# MP-Support.net
KiCad netlist of a schematic drawn in Altium Designer
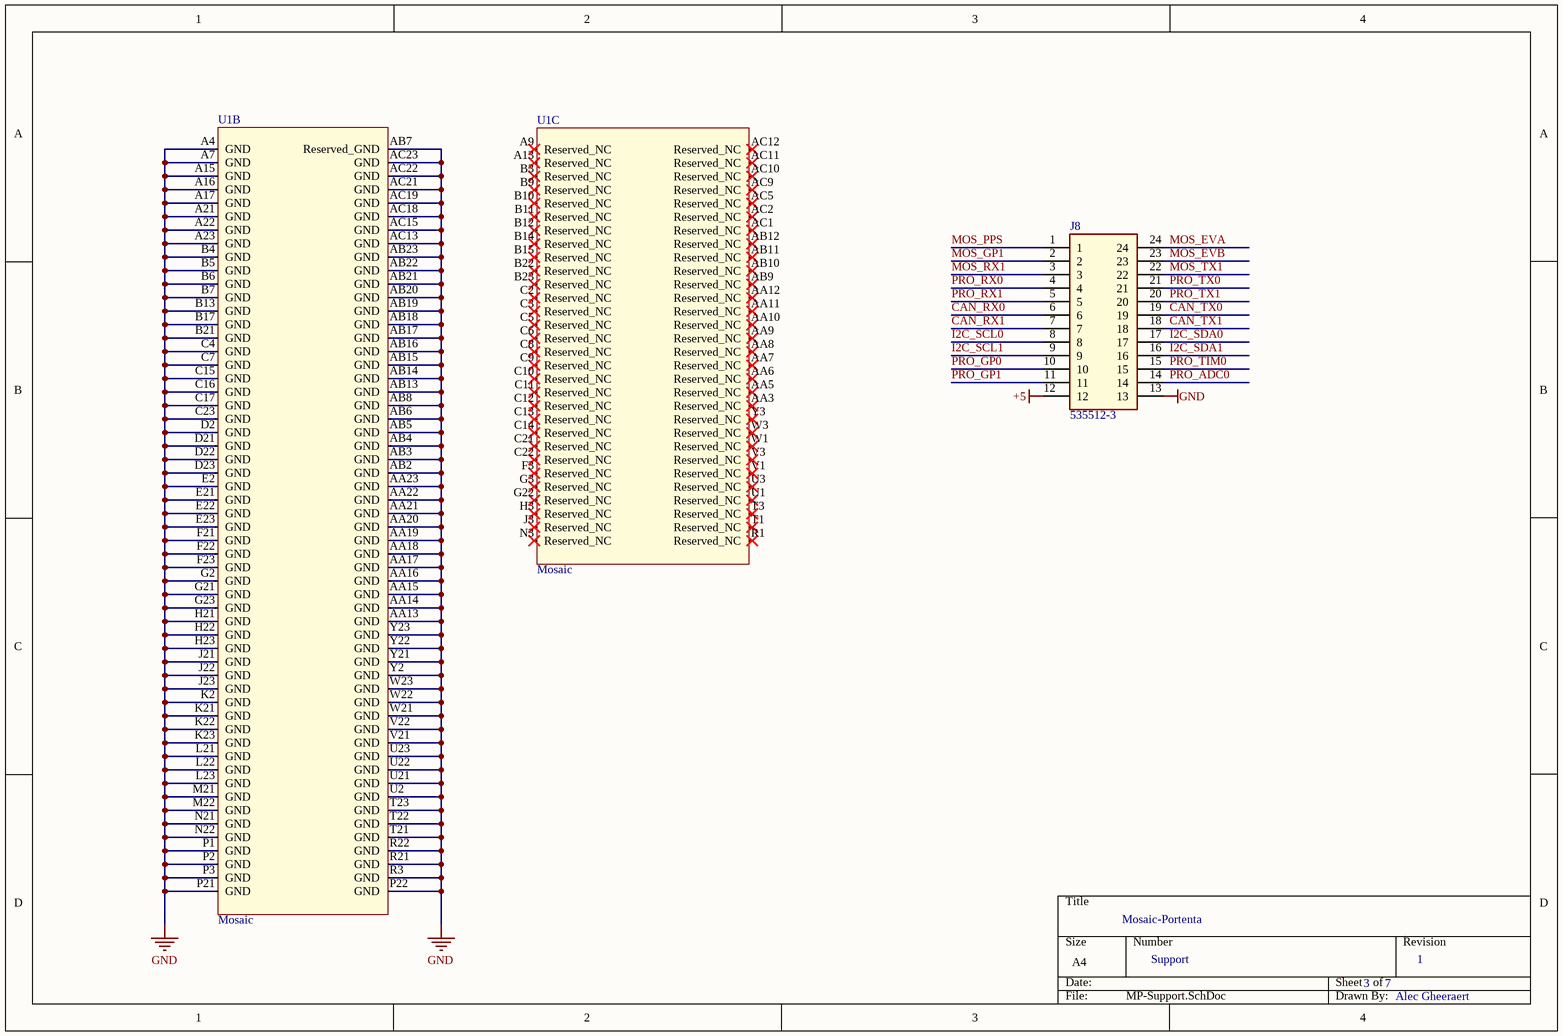
[diagram p0: MP-Support.SchDoc]

(export (version "E")
  (design (tool "Eeschema 10.0.6"))
  (components
    (comp (ref "J8")
      (value "535512-3")
      (footprint "5355123")
      (description "24 Pin Right Angle Female Header")
      (libsource (lib "Ghrt") (part "535512-3"))
    )
    (comp (ref "U1")
      (value "Mosaic")
      (footprint "Mosaic")
      (description "GNSS RTK Receiver")
      (fields (field (name "MANUFACTURER") "Septentrio"))
      (libsource (lib "Ghrt") (part "CMP-00013-3"))
    )
  )
  (nets
    (net (code "1") (name "+5") (class "Default")
      (node (ref "J8") (pin "12") (pinfunction "12_12") (pintype "passive"))
    )
    (net (code "2") (name "/CAN_RX0") (class "Default")
      (node (ref "J8") (pin "6") (pinfunction "6_6") (pintype "passive"))
    )
    (net (code "3") (name "/CAN_RX1") (class "Default")
      (node (ref "J8") (pin "7") (pinfunction "7_7") (pintype "passive"))
    )
    (net (code "4") (name "/CAN_TX0") (class "Default")
      (node (ref "J8") (pin "19") (pinfunction "19_19") (pintype "passive"))
    )
    (net (code "5") (name "/CAN_TX1") (class "Default")
      (node (ref "J8") (pin "18") (pinfunction "18_18") (pintype "passive"))
    )
    (net (code "6") (name "/I2C_SCL0") (class "Default")
      (node (ref "J8") (pin "8") (pinfunction "8_8") (pintype "passive"))
    )
    (net (code "7") (name "/I2C_SCL1") (class "Default")
      (node (ref "J8") (pin "9") (pinfunction "9_9") (pintype "passive"))
    )
    (net (code "8") (name "/I2C_SDA0") (class "Default")
      (node (ref "J8") (pin "17") (pinfunction "17_17") (pintype "passive"))
    )
    (net (code "9") (name "/I2C_SDA1") (class "Default")
      (node (ref "J8") (pin "16") (pinfunction "16_16") (pintype "passive"))
    )
    (net (code "10") (name "/MOS_EVA") (class "Default")
      (node (ref "J8") (pin "24") (pinfunction "24_24") (pintype "passive"))
    )
    (net (code "11") (name "/MOS_EVB") (class "Default")
      (node (ref "J8") (pin "23") (pinfunction "23_23") (pintype "passive"))
    )
    (net (code "12") (name "/MOS_GP1") (class "Default")
      (node (ref "J8") (pin "2") (pinfunction "2_2") (pintype "passive"))
    )
    (net (code "13") (name "/MOS_PPS") (class "Default")
      (node (ref "J8") (pin "1") (pinfunction "1_1") (pintype "passive"))
    )
    (net (code "14") (name "/MOS_RX1") (class "Default")
      (node (ref "J8") (pin "3") (pinfunction "3_3") (pintype "passive"))
    )
    (net (code "15") (name "/MOS_TX1") (class "Default")
      (node (ref "J8") (pin "22") (pinfunction "22_22") (pintype "passive"))
    )
    (net (code "16") (name "/PRO_ADC0") (class "Default")
      (node (ref "J8") (pin "14") (pinfunction "14_14") (pintype "passive"))
    )
    (net (code "17") (name "/PRO_GP0") (class "Default")
      (node (ref "J8") (pin "10") (pinfunction "10_10") (pintype "passive"))
    )
    (net (code "18") (name "/PRO_GP1") (class "Default")
      (node (ref "J8") (pin "11") (pinfunction "11_11") (pintype "passive"))
    )
    (net (code "19") (name "/PRO_RX0") (class "Default")
      (node (ref "J8") (pin "4") (pinfunction "4_4") (pintype "passive"))
    )
    (net (code "20") (name "/PRO_RX1") (class "Default")
      (node (ref "J8") (pin "5") (pinfunction "5_5") (pintype "passive"))
    )
    (net (code "21") (name "/PRO_TIM0") (class "Default")
      (node (ref "J8") (pin "15") (pinfunction "15_15") (pintype "passive"))
    )
    (net (code "22") (name "/PRO_TX0") (class "Default")
      (node (ref "J8") (pin "21") (pinfunction "21_21") (pintype "passive"))
    )
    (net (code "23") (name "/PRO_TX1") (class "Default")
      (node (ref "J8") (pin "20") (pinfunction "20_20") (pintype "passive"))
    )
    (net (code "24") (name "GND") (class "Default")
      (node (ref "J8") (pin "13") (pinfunction "13_13") (pintype "passive"))
      (node (ref "U1") (pin "A15") (pinfunction "GND_A15") (pintype "power_in"))
      (node (ref "U1") (pin "A16") (pinfunction "GND_A16") (pintype "power_in"))
      (node (ref "U1") (pin "A17") (pinfunction "GND_A17") (pintype "power_in"))
      (node (ref "U1") (pin "A21") (pinfunction "GND_A21") (pintype "power_in"))
      (node (ref "U1") (pin "A22") (pinfunction "GND_A22") (pintype "power_in"))
      (node (ref "U1") (pin "A23") (pinfunction "GND_A23") (pintype "power_in"))
      (node (ref "U1") (pin "A4") (pinfunction "GND_A4") (pintype "power_in"))
      (node (ref "U1") (pin "A7") (pinfunction "GND_A7") (pintype "power_in"))
      (node (ref "U1") (pin "AA13") (pinfunction "GND_AA13") (pintype "power_in"))
      (node (ref "U1") (pin "AA14") (pinfunction "GND_AA14") (pintype "power_in"))
      (node (ref "U1") (pin "AA15") (pinfunction "GND_AA15") (pintype "power_in"))
      (node (ref "U1") (pin "AA16") (pinfunction "GND_AA16") (pintype "power_in"))
      (node (ref "U1") (pin "AA17") (pinfunction "GND_AA17") (pintype "power_in"))
      (node (ref "U1") (pin "AA18") (pinfunction "GND_AA18") (pintype "power_in"))
      (node (ref "U1") (pin "AA19") (pinfunction "GND_AA19") (pintype "power_in"))
      (node (ref "U1") (pin "AA20") (pinfunction "GND_AA20") (pintype "power_in"))
      (node (ref "U1") (pin "AA21") (pinfunction "GND_AA21") (pintype "power_in"))
      (node (ref "U1") (pin "AA22") (pinfunction "GND_AA22") (pintype "power_in"))
      (node (ref "U1") (pin "AA23") (pinfunction "GND_AA23") (pintype "power_in"))
      (node (ref "U1") (pin "AB13") (pinfunction "GND_AB13") (pintype "power_in"))
      (node (ref "U1") (pin "AB14") (pinfunction "GND_AB14") (pintype "power_in"))
      (node (ref "U1") (pin "AB15") (pinfunction "GND_AB15") (pintype "power_in"))
      (node (ref "U1") (pin "AB16") (pinfunction "GND_AB16") (pintype "power_in"))
      (node (ref "U1") (pin "AB17") (pinfunction "GND_AB17") (pintype "power_in"))
      (node (ref "U1") (pin "AB18") (pinfunction "GND_AB18") (pintype "power_in"))
      (node (ref "U1") (pin "AB19") (pinfunction "GND_AB19") (pintype "power_in"))
      (node (ref "U1") (pin "AB2") (pinfunction "GND_AB2") (pintype "power_in"))
      (node (ref "U1") (pin "AB20") (pinfunction "GND_AB20") (pintype "power_in"))
      (node (ref "U1") (pin "AB21") (pinfunction "GND_AB21") (pintype "power_in"))
      (node (ref "U1") (pin "AB22") (pinfunction "GND_AB22") (pintype "power_in"))
      (node (ref "U1") (pin "AB23") (pinfunction "GND_AB23") (pintype "power_in"))
      (node (ref "U1") (pin "AB3") (pinfunction "GND_AB3") (pintype "power_in"))
      (node (ref "U1") (pin "AB4") (pinfunction "GND_AB4") (pintype "power_in"))
      (node (ref "U1") (pin "AB5") (pinfunction "GND_AB5") (pintype "power_in"))
      (node (ref "U1") (pin "AB6") (pinfunction "GND_AB6") (pintype "power_in"))
      (node (ref "U1") (pin "AB7") (pinfunction "Reserved_GND_AB7") (pintype "power_in"))
      (node (ref "U1") (pin "AB8") (pinfunction "GND_AB8") (pintype "power_in"))
      (node (ref "U1") (pin "AC13") (pinfunction "GND_AC13") (pintype "power_in"))
      (node (ref "U1") (pin "AC15") (pinfunction "GND_AC15") (pintype "power_in"))
      (node (ref "U1") (pin "AC18") (pinfunction "GND_AC18") (pintype "power_in"))
      (node (ref "U1") (pin "AC19") (pinfunction "GND_AC19") (pintype "power_in"))
      (node (ref "U1") (pin "AC21") (pinfunction "GND_AC21") (pintype "power_in"))
      (node (ref "U1") (pin "AC22") (pinfunction "GND_AC22") (pintype "power_in"))
      (node (ref "U1") (pin "AC23") (pinfunction "GND_AC23") (pintype "power_in"))
      (node (ref "U1") (pin "B13") (pinfunction "GND_B13") (pintype "power_in"))
      (node (ref "U1") (pin "B17") (pinfunction "GND_B17") (pintype "power_in"))
      (node (ref "U1") (pin "B21") (pinfunction "GND_B21") (pintype "power_in"))
      (node (ref "U1") (pin "B4") (pinfunction "GND_B4") (pintype "power_in"))
      (node (ref "U1") (pin "B5") (pinfunction "GND_B5") (pintype "power_in"))
      (node (ref "U1") (pin "B6") (pinfunction "GND_B6") (pintype "power_in"))
      (node (ref "U1") (pin "B7") (pinfunction "GND_B7") (pintype "power_in"))
      (node (ref "U1") (pin "C15") (pinfunction "GND_C15") (pintype "power_in"))
      (node (ref "U1") (pin "C16") (pinfunction "GND_C16") (pintype "power_in"))
      (node (ref "U1") (pin "C17") (pinfunction "GND_C17") (pintype "power_in"))
      (node (ref "U1") (pin "C23") (pinfunction "GND_C23") (pintype "power_in"))
      (node (ref "U1") (pin "C4") (pinfunction "GND_C4") (pintype "power_in"))
      (node (ref "U1") (pin "C7") (pinfunction "GND_C7") (pintype "power_in"))
      (node (ref "U1") (pin "D2") (pinfunction "GND_D2") (pintype "power_in"))
      (node (ref "U1") (pin "D21") (pinfunction "GND_D21") (pintype "power_in"))
      (node (ref "U1") (pin "D22") (pinfunction "GND_D22") (pintype "power_in"))
      (node (ref "U1") (pin "D23") (pinfunction "GND_D23") (pintype "power_in"))
      (node (ref "U1") (pin "E2") (pinfunction "GND_E2") (pintype "power_in"))
      (node (ref "U1") (pin "E21") (pinfunction "GND_E21") (pintype "power_in"))
      (node (ref "U1") (pin "E22") (pinfunction "GND_E22") (pintype "power_in"))
      (node (ref "U1") (pin "E23") (pinfunction "GND_E23") (pintype "power_in"))
      (node (ref "U1") (pin "F21") (pinfunction "GND_F21") (pintype "power_in"))
      (node (ref "U1") (pin "F22") (pinfunction "GND_F22") (pintype "power_in"))
      (node (ref "U1") (pin "F23") (pinfunction "GND_F23") (pintype "power_in"))
      (node (ref "U1") (pin "G2") (pinfunction "GND_G2") (pintype "power_in"))
      (node (ref "U1") (pin "G21") (pinfunction "GND_G21") (pintype "power_in"))
      (node (ref "U1") (pin "G23") (pinfunction "GND_G23") (pintype "power_in"))
      (node (ref "U1") (pin "H21") (pinfunction "GND_H21") (pintype "power_in"))
      (node (ref "U1") (pin "H22") (pinfunction "GND_H22") (pintype "power_in"))
      (node (ref "U1") (pin "H23") (pinfunction "GND_H23") (pintype "power_in"))
      (node (ref "U1") (pin "J21") (pinfunction "GND_J21") (pintype "power_in"))
      (node (ref "U1") (pin "J22") (pinfunction "GND_J22") (pintype "power_in"))
      (node (ref "U1") (pin "J23") (pinfunction "GND_J23") (pintype "power_in"))
      (node (ref "U1") (pin "K2") (pinfunction "GND_K2") (pintype "power_in"))
      (node (ref "U1") (pin "K21") (pinfunction "GND_K21") (pintype "power_in"))
      (node (ref "U1") (pin "K22") (pinfunction "GND_K22") (pintype "power_in"))
      (node (ref "U1") (pin "K23") (pinfunction "GND_K23") (pintype "power_in"))
      (node (ref "U1") (pin "L21") (pinfunction "GND_L21") (pintype "power_in"))
      (node (ref "U1") (pin "L22") (pinfunction "GND_L22") (pintype "power_in"))
      (node (ref "U1") (pin "L23") (pinfunction "GND_L23") (pintype "power_in"))
      (node (ref "U1") (pin "M21") (pinfunction "GND_M21") (pintype "power_in"))
      (node (ref "U1") (pin "M22") (pinfunction "GND_M22") (pintype "power_in"))
      (node (ref "U1") (pin "N21") (pinfunction "GND_N21") (pintype "power_in"))
      (node (ref "U1") (pin "N22") (pinfunction "GND_N22") (pintype "power_in"))
      (node (ref "U1") (pin "P1") (pinfunction "GND_P1") (pintype "power_in"))
      (node (ref "U1") (pin "P2") (pinfunction "GND_P2") (pintype "power_in"))
      (node (ref "U1") (pin "P21") (pinfunction "GND_P21") (pintype "power_in"))
      (node (ref "U1") (pin "P22") (pinfunction "GND_P22") (pintype "power_in"))
      (node (ref "U1") (pin "P3") (pinfunction "GND_P3") (pintype "power_in"))
      (node (ref "U1") (pin "R21") (pinfunction "GND_R21") (pintype "power_in"))
      (node (ref "U1") (pin "R22") (pinfunction "GND_R22") (pintype "power_in"))
      (node (ref "U1") (pin "R3") (pinfunction "GND_R3") (pintype "power_in"))
      (node (ref "U1") (pin "T21") (pinfunction "GND_T21") (pintype "power_in"))
      (node (ref "U1") (pin "T22") (pinfunction "GND_T22") (pintype "power_in"))
      (node (ref "U1") (pin "T23") (pinfunction "GND_T23") (pintype "power_in"))
      (node (ref "U1") (pin "U2") (pinfunction "GND_U2") (pintype "power_in"))
      (node (ref "U1") (pin "U21") (pinfunction "GND_U21") (pintype "power_in"))
      (node (ref "U1") (pin "U22") (pinfunction "GND_U22") (pintype "power_in"))
      (node (ref "U1") (pin "U23") (pinfunction "GND_U23") (pintype "power_in"))
      (node (ref "U1") (pin "V21") (pinfunction "GND_V21") (pintype "power_in"))
      (node (ref "U1") (pin "V22") (pinfunction "GND_V22") (pintype "power_in"))
      (node (ref "U1") (pin "W21") (pinfunction "GND_W21") (pintype "power_in"))
      (node (ref "U1") (pin "W22") (pinfunction "GND_W22") (pintype "power_in"))
      (node (ref "U1") (pin "W23") (pinfunction "GND_W23") (pintype "power_in"))
      (node (ref "U1") (pin "Y2") (pinfunction "GND_Y2") (pintype "power_in"))
      (node (ref "U1") (pin "Y21") (pinfunction "GND_Y21") (pintype "power_in"))
      (node (ref "U1") (pin "Y22") (pinfunction "GND_Y22") (pintype "power_in"))
      (node (ref "U1") (pin "Y23") (pinfunction "GND_Y23") (pintype "power_in"))
    )
    (net (code "25") (name "unconnected-(U1C-Reserved_NC-PadA9)") (class "Default")
      (node (ref "U1") (pin "A9") (pinfunction "Reserved_NC_A9") (pintype "passive+no_connect"))
    )
    (net (code "26") (name "unconnected-(U1C-Reserved_NC-PadA13)") (class "Default")
      (node (ref "U1") (pin "A13") (pinfunction "Reserved_NC_A13") (pintype "passive+no_connect"))
    )
    (net (code "27") (name "unconnected-(U1C-Reserved_NC-PadAA3)") (class "Default")
      (node (ref "U1") (pin "AA3") (pinfunction "Reserved_NC_AA3") (pintype "passive+no_connect"))
    )
    (net (code "28") (name "unconnected-(U1C-Reserved_NC-PadAA5)") (class "Default")
      (node (ref "U1") (pin "AA5") (pinfunction "Reserved_NC_AA5") (pintype "passive+no_connect"))
    )
    (net (code "29") (name "unconnected-(U1C-Reserved_NC-PadAA6)") (class "Default")
      (node (ref "U1") (pin "AA6") (pinfunction "Reserved_NC_AA6") (pintype "passive+no_connect"))
    )
    (net (code "30") (name "unconnected-(U1C-Reserved_NC-PadAA7)") (class "Default")
      (node (ref "U1") (pin "AA7") (pinfunction "Reserved_NC_AA7") (pintype "passive+no_connect"))
    )
    (net (code "31") (name "unconnected-(U1C-Reserved_NC-PadAA8)") (class "Default")
      (node (ref "U1") (pin "AA8") (pinfunction "Reserved_NC_AA8") (pintype "passive+no_connect"))
    )
    (net (code "32") (name "unconnected-(U1C-Reserved_NC-PadAA9)") (class "Default")
      (node (ref "U1") (pin "AA9") (pinfunction "Reserved_NC_AA9") (pintype "passive+no_connect"))
    )
    (net (code "33") (name "unconnected-(U1C-Reserved_NC-PadAA10)") (class "Default")
      (node (ref "U1") (pin "AA10") (pinfunction "Reserved_NC_AA10") (pintype "passive+no_connect"))
    )
    (net (code "34") (name "unconnected-(U1C-Reserved_NC-PadAA11)") (class "Default")
      (node (ref "U1") (pin "AA11") (pinfunction "Reserved_NC_AA11") (pintype "passive+no_connect"))
    )
    (net (code "35") (name "unconnected-(U1C-Reserved_NC-PadAA12)") (class "Default")
      (node (ref "U1") (pin "AA12") (pinfunction "Reserved_NC_AA12") (pintype "passive+no_connect"))
    )
    (net (code "36") (name "unconnected-(U1C-Reserved_NC-PadAB9)") (class "Default")
      (node (ref "U1") (pin "AB9") (pinfunction "Reserved_NC_AB9") (pintype "passive+no_connect"))
    )
    (net (code "37") (name "unconnected-(U1C-Reserved_NC-PadAB10)") (class "Default")
      (node (ref "U1") (pin "AB10") (pinfunction "Reserved_NC_AB10") (pintype "passive+no_connect"))
    )
    (net (code "38") (name "unconnected-(U1C-Reserved_NC-PadAB11)") (class "Default")
      (node (ref "U1") (pin "AB11") (pinfunction "Reserved_NC_AB11") (pintype "passive+no_connect"))
    )
    (net (code "39") (name "unconnected-(U1C-Reserved_NC-PadAB12)") (class "Default")
      (node (ref "U1") (pin "AB12") (pinfunction "Reserved_NC_AB12") (pintype "passive+no_connect"))
    )
    (net (code "40") (name "unconnected-(U1C-Reserved_NC-PadAC1)") (class "Default")
      (node (ref "U1") (pin "AC1") (pinfunction "Reserved_NC_AC1") (pintype "passive+no_connect"))
    )
    (net (code "41") (name "unconnected-(U1C-Reserved_NC-PadAC2)") (class "Default")
      (node (ref "U1") (pin "AC2") (pinfunction "Reserved_NC_AC2") (pintype "passive+no_connect"))
    )
    (net (code "42") (name "unconnected-(U1C-Reserved_NC-PadAC5)") (class "Default")
      (node (ref "U1") (pin "AC5") (pinfunction "Reserved_NC_AC5") (pintype "passive+no_connect"))
    )
    (net (code "43") (name "unconnected-(U1C-Reserved_NC-PadAC9)") (class "Default")
      (node (ref "U1") (pin "AC9") (pinfunction "Reserved_NC_AC9") (pintype "passive+no_connect"))
    )
    (net (code "44") (name "unconnected-(U1C-Reserved_NC-PadAC10)") (class "Default")
      (node (ref "U1") (pin "AC10") (pinfunction "Reserved_NC_AC10") (pintype "passive+no_connect"))
    )
    (net (code "45") (name "unconnected-(U1C-Reserved_NC-PadAC11)") (class "Default")
      (node (ref "U1") (pin "AC11") (pinfunction "Reserved_NC_AC11") (pintype "passive+no_connect"))
    )
    (net (code "46") (name "unconnected-(U1C-Reserved_NC-PadAC12)") (class "Default")
      (node (ref "U1") (pin "AC12") (pinfunction "Reserved_NC_AC12") (pintype "passive+no_connect"))
    )
    (net (code "47") (name "unconnected-(U1C-Reserved_NC-PadB3)") (class "Default")
      (node (ref "U1") (pin "B3") (pinfunction "Reserved_NC_B3") (pintype "passive+no_connect"))
    )
    (net (code "48") (name "unconnected-(U1C-Reserved_NC-PadB9)") (class "Default")
      (node (ref "U1") (pin "B9") (pinfunction "Reserved_NC_B9") (pintype "passive+no_connect"))
    )
    (net (code "49") (name "unconnected-(U1C-Reserved_NC-PadB10)") (class "Default")
      (node (ref "U1") (pin "B10") (pinfunction "Reserved_NC_B10") (pintype "passive+no_connect"))
    )
    (net (code "50") (name "unconnected-(U1C-Reserved_NC-PadB11)") (class "Default")
      (node (ref "U1") (pin "B11") (pinfunction "Reserved_NC_B11") (pintype "passive+no_connect"))
    )
    (net (code "51") (name "unconnected-(U1C-Reserved_NC-PadB12)") (class "Default")
      (node (ref "U1") (pin "B12") (pinfunction "Reserved_NC_B12") (pintype "passive+no_connect"))
    )
    (net (code "52") (name "unconnected-(U1C-Reserved_NC-PadB14)") (class "Default")
      (node (ref "U1") (pin "B14") (pinfunction "Reserved_NC_B14") (pintype "passive+no_connect"))
    )
    (net (code "53") (name "unconnected-(U1C-Reserved_NC-PadB15)") (class "Default")
      (node (ref "U1") (pin "B15") (pinfunction "Reserved_NC_B15") (pintype "passive+no_connect"))
    )
    (net (code "54") (name "unconnected-(U1C-Reserved_NC-PadB22)") (class "Default")
      (node (ref "U1") (pin "B22") (pinfunction "Reserved_NC_B22") (pintype "passive+no_connect"))
    )
    (net (code "55") (name "unconnected-(U1C-Reserved_NC-PadB23)") (class "Default")
      (node (ref "U1") (pin "B23") (pinfunction "Reserved_NC_B23") (pintype "passive+no_connect"))
    )
    (net (code "56") (name "unconnected-(U1C-Reserved_NC-PadC2)") (class "Default")
      (node (ref "U1") (pin "C2") (pinfunction "Reserved_NC_C2") (pintype "passive+no_connect"))
    )
    (net (code "57") (name "unconnected-(U1C-Reserved_NC-PadC3)") (class "Default")
      (node (ref "U1") (pin "C3") (pinfunction "Reserved_NC_C3") (pintype "passive+no_connect"))
    )
    (net (code "58") (name "unconnected-(U1C-Reserved_NC-PadC5)") (class "Default")
      (node (ref "U1") (pin "C5") (pinfunction "Reserved_NC_C5") (pintype "passive+no_connect"))
    )
    (net (code "59") (name "unconnected-(U1C-Reserved_NC-PadC6)") (class "Default")
      (node (ref "U1") (pin "C6") (pinfunction "Reserved_NC_C6") (pintype "passive+no_connect"))
    )
    (net (code "60") (name "unconnected-(U1C-Reserved_NC-PadC8)") (class "Default")
      (node (ref "U1") (pin "C8") (pinfunction "Reserved_NC_C8") (pintype "passive+no_connect"))
    )
    (net (code "61") (name "unconnected-(U1C-Reserved_NC-PadC9)") (class "Default")
      (node (ref "U1") (pin "C9") (pinfunction "Reserved_NC_C9") (pintype "passive+no_connect"))
    )
    (net (code "62") (name "unconnected-(U1C-Reserved_NC-PadC10)") (class "Default")
      (node (ref "U1") (pin "C10") (pinfunction "Reserved_NC_C10") (pintype "passive+no_connect"))
    )
    (net (code "63") (name "unconnected-(U1C-Reserved_NC-PadC11)") (class "Default")
      (node (ref "U1") (pin "C11") (pinfunction "Reserved_NC_C11") (pintype "passive+no_connect"))
    )
    (net (code "64") (name "unconnected-(U1C-Reserved_NC-PadC12)") (class "Default")
      (node (ref "U1") (pin "C12") (pinfunction "Reserved_NC_C12") (pintype "passive+no_connect"))
    )
    (net (code "65") (name "unconnected-(U1C-Reserved_NC-PadC13)") (class "Default")
      (node (ref "U1") (pin "C13") (pinfunction "Reserved_NC_C13") (pintype "passive+no_connect"))
    )
    (net (code "66") (name "unconnected-(U1C-Reserved_NC-PadC14)") (class "Default")
      (node (ref "U1") (pin "C14") (pinfunction "Reserved_NC_C14") (pintype "passive+no_connect"))
    )
    (net (code "67") (name "unconnected-(U1C-Reserved_NC-PadC21)") (class "Default")
      (node (ref "U1") (pin "C21") (pinfunction "Reserved_NC_C21") (pintype "passive+no_connect"))
    )
    (net (code "68") (name "unconnected-(U1C-Reserved_NC-PadC22)") (class "Default")
      (node (ref "U1") (pin "C22") (pinfunction "Reserved_NC_C22") (pintype "passive+no_connect"))
    )
    (net (code "69") (name "unconnected-(U1C-Reserved_NC-PadF3)") (class "Default")
      (node (ref "U1") (pin "F3") (pinfunction "Reserved_NC_F3") (pintype "passive+no_connect"))
    )
    (net (code "70") (name "unconnected-(U1C-Reserved_NC-PadG3)") (class "Default")
      (node (ref "U1") (pin "G3") (pinfunction "Reserved_NC_G3") (pintype "passive+no_connect"))
    )
    (net (code "71") (name "unconnected-(U1C-Reserved_NC-PadG22)") (class "Default")
      (node (ref "U1") (pin "G22") (pinfunction "Reserved_NC_G22") (pintype "passive+no_connect"))
    )
    (net (code "72") (name "unconnected-(U1C-Reserved_NC-PadH3)") (class "Default")
      (node (ref "U1") (pin "H3") (pinfunction "Reserved_NC_H3") (pintype "passive+no_connect"))
    )
    (net (code "73") (name "unconnected-(U1C-Reserved_NC-PadJ3)") (class "Default")
      (node (ref "U1") (pin "J3") (pinfunction "Reserved_NC_J3") (pintype "passive+no_connect"))
    )
    (net (code "74") (name "unconnected-(U1C-Reserved_NC-PadN3)") (class "Default")
      (node (ref "U1") (pin "N3") (pinfunction "Reserved_NC_N3") (pintype "passive+no_connect"))
    )
    (net (code "75") (name "unconnected-(U1C-Reserved_NC-PadR1)") (class "Default")
      (node (ref "U1") (pin "R1") (pinfunction "Reserved_NC_R1") (pintype "passive+no_connect"))
    )
    (net (code "76") (name "unconnected-(U1C-Reserved_NC-PadT1)") (class "Default")
      (node (ref "U1") (pin "T1") (pinfunction "Reserved_NC_T1") (pintype "passive+no_connect"))
    )
    (net (code "77") (name "unconnected-(U1C-Reserved_NC-PadT3)") (class "Default")
      (node (ref "U1") (pin "T3") (pinfunction "Reserved_NC_T3") (pintype "passive+no_connect"))
    )
    (net (code "78") (name "unconnected-(U1C-Reserved_NC-PadU1)") (class "Default")
      (node (ref "U1") (pin "U1") (pinfunction "Reserved_NC_U1") (pintype "passive+no_connect"))
    )
    (net (code "79") (name "unconnected-(U1C-Reserved_NC-PadU3)") (class "Default")
      (node (ref "U1") (pin "U3") (pinfunction "Reserved_NC_U3") (pintype "passive+no_connect"))
    )
    (net (code "80") (name "unconnected-(U1C-Reserved_NC-PadV1)") (class "Default")
      (node (ref "U1") (pin "V1") (pinfunction "Reserved_NC_V1") (pintype "passive+no_connect"))
    )
    (net (code "81") (name "unconnected-(U1C-Reserved_NC-PadV3)") (class "Default")
      (node (ref "U1") (pin "V3") (pinfunction "Reserved_NC_V3") (pintype "passive+no_connect"))
    )
    (net (code "82") (name "unconnected-(U1C-Reserved_NC-PadW1)") (class "Default")
      (node (ref "U1") (pin "W1") (pinfunction "Reserved_NC_W1") (pintype "passive+no_connect"))
    )
    (net (code "83") (name "unconnected-(U1C-Reserved_NC-PadW3)") (class "Default")
      (node (ref "U1") (pin "W3") (pinfunction "Reserved_NC_W3") (pintype "passive+no_connect"))
    )
    (net (code "84") (name "unconnected-(U1C-Reserved_NC-PadY3)") (class "Default")
      (node (ref "U1") (pin "Y3") (pinfunction "Reserved_NC_Y3") (pintype "passive+no_connect"))
    )
  )
)
